# LampMatrixShield.net
KiCad netlist of a schematic drawn in EAGLE
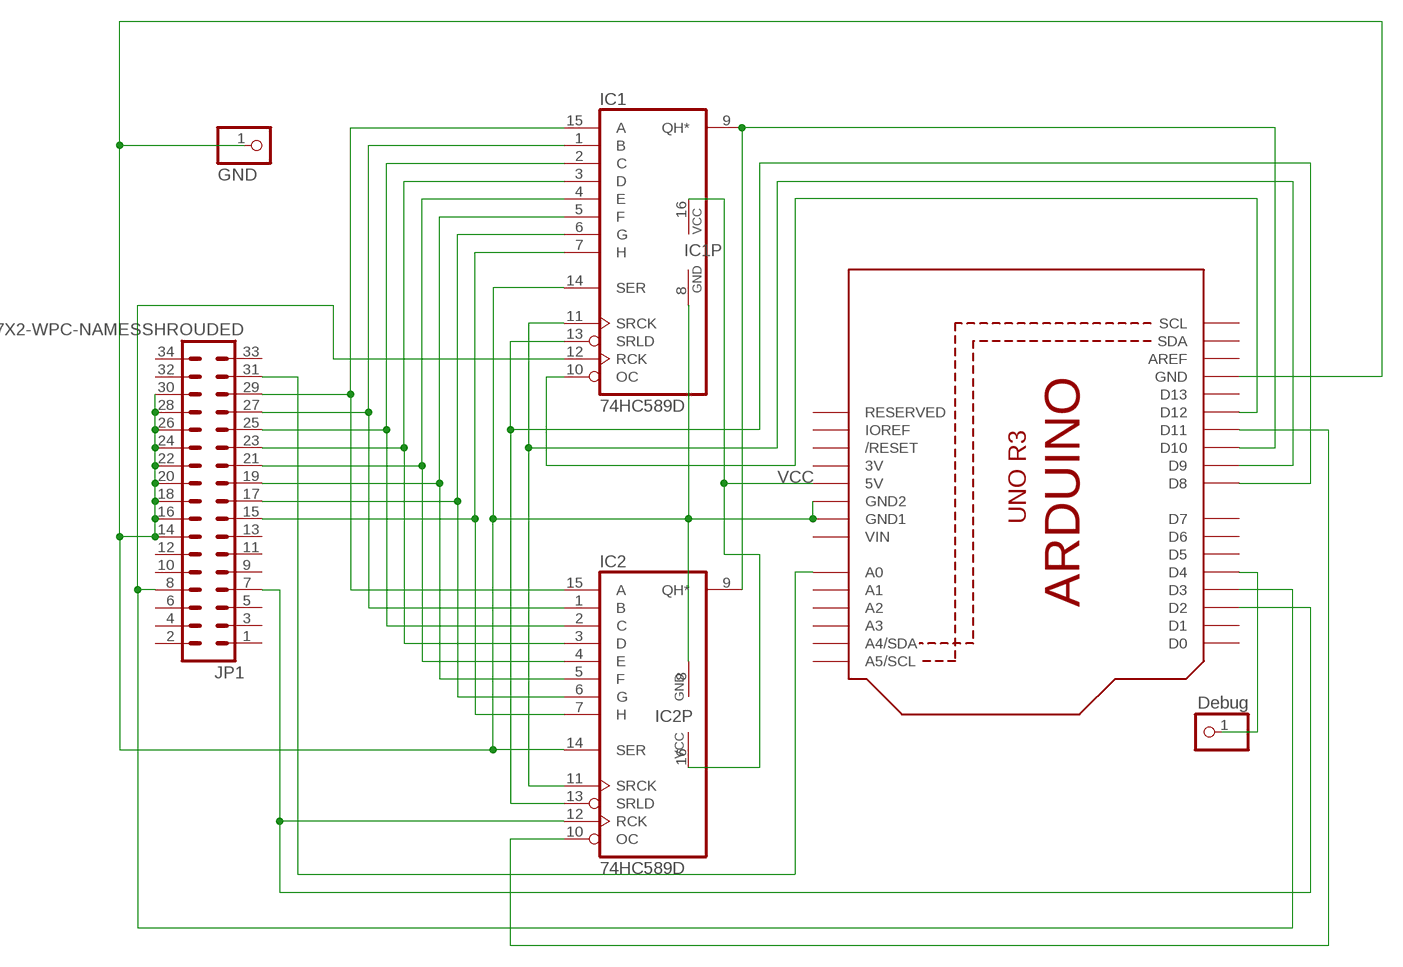
[diagram p0: schematic, sheet 1]

(export (version "E")
  (design (tool "Eeschema 10.0.6"))
  (components
    (comp (ref "IC1")
      (value "74HC589D")
      (footprint "eagle-import:SO16")
      (libsource (lib "eagle-import") (part "74589DHC"))
    )
    (comp (ref "IC2")
      (value "74HC589D")
      (footprint "eagle-import:SO16")
      (libsource (lib "eagle-import") (part "74589DHC"))
    )
    (comp (ref "JP1")
      (value "M17X2-WPC-NAMESSHROUDED")
      (footprint "eagle-import:2X17_SHROUDED")
      (libsource (lib "eagle-import") (part "M17X2-WPC-NAMESSHROUDED"))
    )
    (comp (ref "JP2")
      (value "GND")
      (footprint "eagle-import:1X01-CLEANBIG")
      (libsource (lib "eagle-import") (part "PINHD-1X1CB"))
    )
    (comp (ref "JP3")
      (value "Debug")
      (footprint "eagle-import:1X01-CLEANBIG")
      (libsource (lib "eagle-import") (part "PINHD-1X1CB"))
    )
    (comp (ref "U1")
      (value "ARDUINOR3-BPLACE")
      (footprint "eagle-import:ARDUINOR3-BPLACE")
      (libsource (lib "eagle-import") (part "ARDUINOR3-BPLACE"))
    )
  )
  (nets
    (net (code "1") (name "/3V") (class "Default")
      (node (ref "U1") (pin "3V") (pinfunction "3V_3V") (pintype "power_in"))
    )
    (net (code "2") (name "/VCC") (class "Default")
      (node (ref "IC1") (pin "16") (pinfunction "VCC_16") (pintype "power_in"))
      (node (ref "IC2") (pin "16") (pinfunction "VCC_16") (pintype "power_in"))
      (node (ref "U1") (pin "5V") (pinfunction "5V_5V") (pintype "power_in"))
    )
    (net (code "3") (name "/VIN") (class "Default")
      (node (ref "U1") (pin "VIN") (pinfunction "VIN_VIN") (pintype "power_in"))
    )
    (net (code "4") (name "Net-(IC1A-A)") (class "Default")
      (node (ref "IC1") (pin "15") (pinfunction "A_15") (pintype "input"))
      (node (ref "IC2") (pin "15") (pinfunction "A_15") (pintype "input"))
      (node (ref "JP1") (pin "29") (pinfunction "29_29") (pintype "passive"))
    )
    (net (code "5") (name "Net-(IC1A-B)") (class "Default")
      (node (ref "IC1") (pin "1") (pinfunction "B_1") (pintype "input"))
      (node (ref "IC2") (pin "1") (pinfunction "B_1") (pintype "input"))
      (node (ref "JP1") (pin "27") (pinfunction "27_27") (pintype "passive"))
    )
    (net (code "6") (name "Net-(IC1A-C)") (class "Default")
      (node (ref "IC1") (pin "2") (pinfunction "C_2") (pintype "input"))
      (node (ref "IC2") (pin "2") (pinfunction "C_2") (pintype "input"))
      (node (ref "JP1") (pin "25") (pinfunction "25_25") (pintype "passive"))
    )
    (net (code "7") (name "Net-(IC1A-D)") (class "Default")
      (node (ref "IC1") (pin "3") (pinfunction "D_3") (pintype "input"))
      (node (ref "IC2") (pin "3") (pinfunction "D_3") (pintype "input"))
      (node (ref "JP1") (pin "23") (pinfunction "23_23") (pintype "passive"))
    )
    (net (code "8") (name "Net-(IC1A-E)") (class "Default")
      (node (ref "IC1") (pin "4") (pinfunction "E_4") (pintype "input"))
      (node (ref "IC2") (pin "4") (pinfunction "E_4") (pintype "input"))
      (node (ref "JP1") (pin "21") (pinfunction "21_21") (pintype "passive"))
    )
    (net (code "9") (name "Net-(IC1A-F)") (class "Default")
      (node (ref "IC1") (pin "5") (pinfunction "F_5") (pintype "input"))
      (node (ref "IC2") (pin "5") (pinfunction "F_5") (pintype "input"))
      (node (ref "JP1") (pin "19") (pinfunction "19_19") (pintype "passive"))
    )
    (net (code "10") (name "Net-(IC1A-G)") (class "Default")
      (node (ref "IC1") (pin "6") (pinfunction "G_6") (pintype "input"))
      (node (ref "IC2") (pin "6") (pinfunction "G_6") (pintype "input"))
      (node (ref "JP1") (pin "17") (pinfunction "17_17") (pintype "passive"))
    )
    (net (code "11") (name "Net-(IC1A-H)") (class "Default")
      (node (ref "IC1") (pin "7") (pinfunction "H_7") (pintype "input"))
      (node (ref "IC2") (pin "7") (pinfunction "H_7") (pintype "input"))
      (node (ref "JP1") (pin "15") (pinfunction "15_15") (pintype "passive"))
    )
    (net (code "12") (name "Net-(IC1A-OC)") (class "Default")
      (node (ref "IC1") (pin "10") (pinfunction "OC_10") (pintype "input"))
      (node (ref "U1") (pin "D12") (pinfunction "D12_D12") (pintype "bidirectional"))
    )
    (net (code "13") (name "Net-(IC1A-QH*)") (class "Default")
      (node (ref "IC1") (pin "9") (pinfunction "QH*_9") (pintype "tri_state"))
      (node (ref "IC2") (pin "9") (pinfunction "QH*_9") (pintype "tri_state"))
      (node (ref "U1") (pin "D10") (pinfunction "D10_D10") (pintype "bidirectional"))
    )
    (net (code "14") (name "Net-(IC1A-RCK)") (class "Default")
      (node (ref "IC1") (pin "12") (pinfunction "RCK_12") (pintype "input"))
      (node (ref "JP1") (pin "8") (pinfunction "8_8") (pintype "passive"))
      (node (ref "U1") (pin "D3") (pinfunction "D3_D3") (pintype "bidirectional"))
    )
    (net (code "15") (name "Net-(IC1A-SER)") (class "Default")
      (node (ref "IC1") (pin "14") (pinfunction "SER_14") (pintype "input"))
      (node (ref "IC1") (pin "8") (pinfunction "GND_8") (pintype "power_in"))
      (node (ref "IC2") (pin "14") (pinfunction "SER_14") (pintype "input"))
      (node (ref "IC2") (pin "8") (pinfunction "GND_8") (pintype "power_in"))
      (node (ref "JP1") (pin "14") (pinfunction "14_14") (pintype "passive"))
      (node (ref "JP1") (pin "16") (pinfunction "16_16") (pintype "passive"))
      (node (ref "JP1") (pin "18") (pinfunction "18_18") (pintype "passive"))
      (node (ref "JP1") (pin "20") (pinfunction "20_20") (pintype "passive"))
      (node (ref "JP1") (pin "22") (pinfunction "22_22") (pintype "passive"))
      (node (ref "JP1") (pin "24") (pinfunction "24_24") (pintype "passive"))
      (node (ref "JP1") (pin "26") (pinfunction "26_26") (pintype "passive"))
      (node (ref "JP1") (pin "28") (pinfunction "28_28") (pintype "passive"))
      (node (ref "JP1") (pin "30") (pinfunction "30_30") (pintype "passive"))
      (node (ref "JP2") (pin "1") (pinfunction "1_1") (pintype "passive"))
      (node (ref "U1") (pin "GND") (pinfunction "GND_GND") (pintype "power_in"))
      (node (ref "U1") (pin "GND1") (pinfunction "GND1_GND1") (pintype "power_in"))
      (node (ref "U1") (pin "GND2") (pinfunction "GND2_GND2") (pintype "power_in"))
    )
    (net (code "16") (name "Net-(IC1A-SRCK)") (class "Default")
      (node (ref "IC1") (pin "11") (pinfunction "SRCK_11") (pintype "input"))
      (node (ref "IC2") (pin "11") (pinfunction "SRCK_11") (pintype "input"))
      (node (ref "U1") (pin "D9") (pinfunction "D9_D9") (pintype "bidirectional"))
    )
    (net (code "17") (name "Net-(IC1A-SRLD)") (class "Default")
      (node (ref "IC1") (pin "13") (pinfunction "SRLD_13") (pintype "input"))
      (node (ref "IC2") (pin "13") (pinfunction "SRLD_13") (pintype "input"))
      (node (ref "U1") (pin "D8") (pinfunction "D8_D8") (pintype "bidirectional"))
    )
    (net (code "18") (name "Net-(IC2A-OC)") (class "Default")
      (node (ref "IC2") (pin "10") (pinfunction "OC_10") (pintype "input"))
      (node (ref "U1") (pin "D11") (pinfunction "D11_D11") (pintype "bidirectional"))
    )
    (net (code "19") (name "Net-(IC2A-RCK)") (class "Default")
      (node (ref "IC2") (pin "12") (pinfunction "RCK_12") (pintype "input"))
      (node (ref "JP1") (pin "7") (pinfunction "7_7") (pintype "passive"))
      (node (ref "U1") (pin "D2") (pinfunction "D2_D2") (pintype "bidirectional"))
    )
    (net (code "20") (name "Net-(JP1-Pad31)") (class "Default")
      (node (ref "JP1") (pin "31") (pinfunction "31_31") (pintype "passive"))
      (node (ref "U1") (pin "A0") (pinfunction "A0_A0") (pintype "bidirectional"))
    )
    (net (code "21") (name "Net-(JP3-Pad1)") (class "Default")
      (node (ref "JP3") (pin "1") (pinfunction "1_1") (pintype "passive"))
      (node (ref "U1") (pin "D4") (pinfunction "D4_D4") (pintype "bidirectional"))
    )
    (net (code "22") (name "unconnected-(JP1-Pad1)") (class "Default")
      (node (ref "JP1") (pin "1") (pinfunction "1_1") (pintype "passive"))
    )
    (net (code "23") (name "unconnected-(JP1-Pad2)") (class "Default")
      (node (ref "JP1") (pin "2") (pinfunction "2_2") (pintype "passive"))
    )
    (net (code "24") (name "unconnected-(JP1-Pad3)") (class "Default")
      (node (ref "JP1") (pin "3") (pinfunction "3_3") (pintype "passive"))
    )
    (net (code "25") (name "unconnected-(JP1-Pad4)") (class "Default")
      (node (ref "JP1") (pin "4") (pinfunction "4_4") (pintype "passive"))
    )
    (net (code "26") (name "unconnected-(JP1-Pad5)") (class "Default")
      (node (ref "JP1") (pin "5") (pinfunction "5_5") (pintype "passive"))
    )
    (net (code "27") (name "unconnected-(JP1-Pad6)") (class "Default")
      (node (ref "JP1") (pin "6") (pinfunction "6_6") (pintype "passive"))
    )
    (net (code "28") (name "unconnected-(JP1-Pad9)") (class "Default")
      (node (ref "JP1") (pin "9") (pinfunction "9_9") (pintype "passive"))
    )
    (net (code "29") (name "unconnected-(JP1-Pad10)") (class "Default")
      (node (ref "JP1") (pin "10") (pinfunction "10_10") (pintype "passive"))
    )
    (net (code "30") (name "unconnected-(JP1-Pad11)") (class "Default")
      (node (ref "JP1") (pin "11") (pinfunction "11_11") (pintype "passive"))
    )
    (net (code "31") (name "unconnected-(JP1-Pad12)") (class "Default")
      (node (ref "JP1") (pin "12") (pinfunction "12_12") (pintype "passive"))
    )
    (net (code "32") (name "unconnected-(JP1-Pad13)") (class "Default")
      (node (ref "JP1") (pin "13") (pinfunction "13_13") (pintype "passive"))
    )
    (net (code "33") (name "unconnected-(JP1-Pad32)") (class "Default")
      (node (ref "JP1") (pin "32") (pinfunction "32_32") (pintype "passive"))
    )
    (net (code "34") (name "unconnected-(JP1-Pad33)") (class "Default")
      (node (ref "JP1") (pin "33") (pinfunction "33_33") (pintype "passive"))
    )
    (net (code "35") (name "unconnected-(JP1-Pad34)") (class "Default")
      (node (ref "JP1") (pin "34") (pinfunction "34_34") (pintype "passive"))
    )
    (net (code "36") (name "unconnected-(U1-A4{slash}SDA-PadA4)") (class "Default")
      (node (ref "U1") (pin "A4") (pinfunction "A4/SDA_A4") (pintype "bidirectional"))
    )
    (net (code "37") (name "unconnected-(U1-A5{slash}SCL-PadA5)") (class "Default")
      (node (ref "U1") (pin "A5") (pinfunction "A5/SCL_A5") (pintype "bidirectional"))
    )
    (net (code "38") (name "unconnected-(U1-PadA1)") (class "Default")
      (node (ref "U1") (pin "A1") (pinfunction "A1_A1") (pintype "bidirectional"))
    )
    (net (code "39") (name "unconnected-(U1-PadA2)") (class "Default")
      (node (ref "U1") (pin "A2") (pinfunction "A2_A2") (pintype "bidirectional"))
    )
    (net (code "40") (name "unconnected-(U1-PadA3)") (class "Default")
      (node (ref "U1") (pin "A3") (pinfunction "A3_A3") (pintype "bidirectional"))
    )
    (net (code "41") (name "unconnected-(U1-PadAREF)") (class "Default")
      (node (ref "U1") (pin "AREF") (pinfunction "AREF_AREF") (pintype "bidirectional"))
    )
    (net (code "42") (name "unconnected-(U1-PadD0)") (class "Default")
      (node (ref "U1") (pin "D0") (pinfunction "D0_D0") (pintype "bidirectional"))
    )
    (net (code "43") (name "unconnected-(U1-PadD1)") (class "Default")
      (node (ref "U1") (pin "D1") (pinfunction "D1_D1") (pintype "bidirectional"))
    )
    (net (code "44") (name "unconnected-(U1-PadD5)") (class "Default")
      (node (ref "U1") (pin "D5") (pinfunction "D5_D5") (pintype "bidirectional"))
    )
    (net (code "45") (name "unconnected-(U1-PadD6)") (class "Default")
      (node (ref "U1") (pin "D6") (pinfunction "D6_D6") (pintype "bidirectional"))
    )
    (net (code "46") (name "unconnected-(U1-PadD7)") (class "Default")
      (node (ref "U1") (pin "D7") (pinfunction "D7_D7") (pintype "bidirectional"))
    )
    (net (code "47") (name "unconnected-(U1-PadD13)") (class "Default")
      (node (ref "U1") (pin "D13") (pinfunction "D13_D13") (pintype "bidirectional"))
    )
    (net (code "48") (name "unconnected-(U1-PadIOREF)") (class "Default")
      (node (ref "U1") (pin "IOREF") (pinfunction "IOREF_IOREF") (pintype "output"))
    )
    (net (code "49") (name "unconnected-(U1-PadRESERVED)") (class "Default")
      (node (ref "U1") (pin "RESERVED") (pinfunction "RESERVED_RESERVED") (pintype "no_connect"))
    )
    (net (code "50") (name "unconnected-(U1-PadSCL)") (class "Default")
      (node (ref "U1") (pin "SCL") (pinfunction "SCL_SCL") (pintype "bidirectional"))
    )
    (net (code "51") (name "unconnected-(U1-PadSDA)") (class "Default")
      (node (ref "U1") (pin "SDA") (pinfunction "SDA_SDA") (pintype "bidirectional"))
    )
    (net (code "52") (name "unconnected-(U1-{slash}RESET-PadRESET)") (class "Default")
      (node (ref "U1") (pin "RESET") (pinfunction "/RESET_RESET") (pintype "bidirectional"))
    )
  )
)
